# lab2_kuchenov_buck.net
KiCad netlist of a schematic drawn in Altium Designer
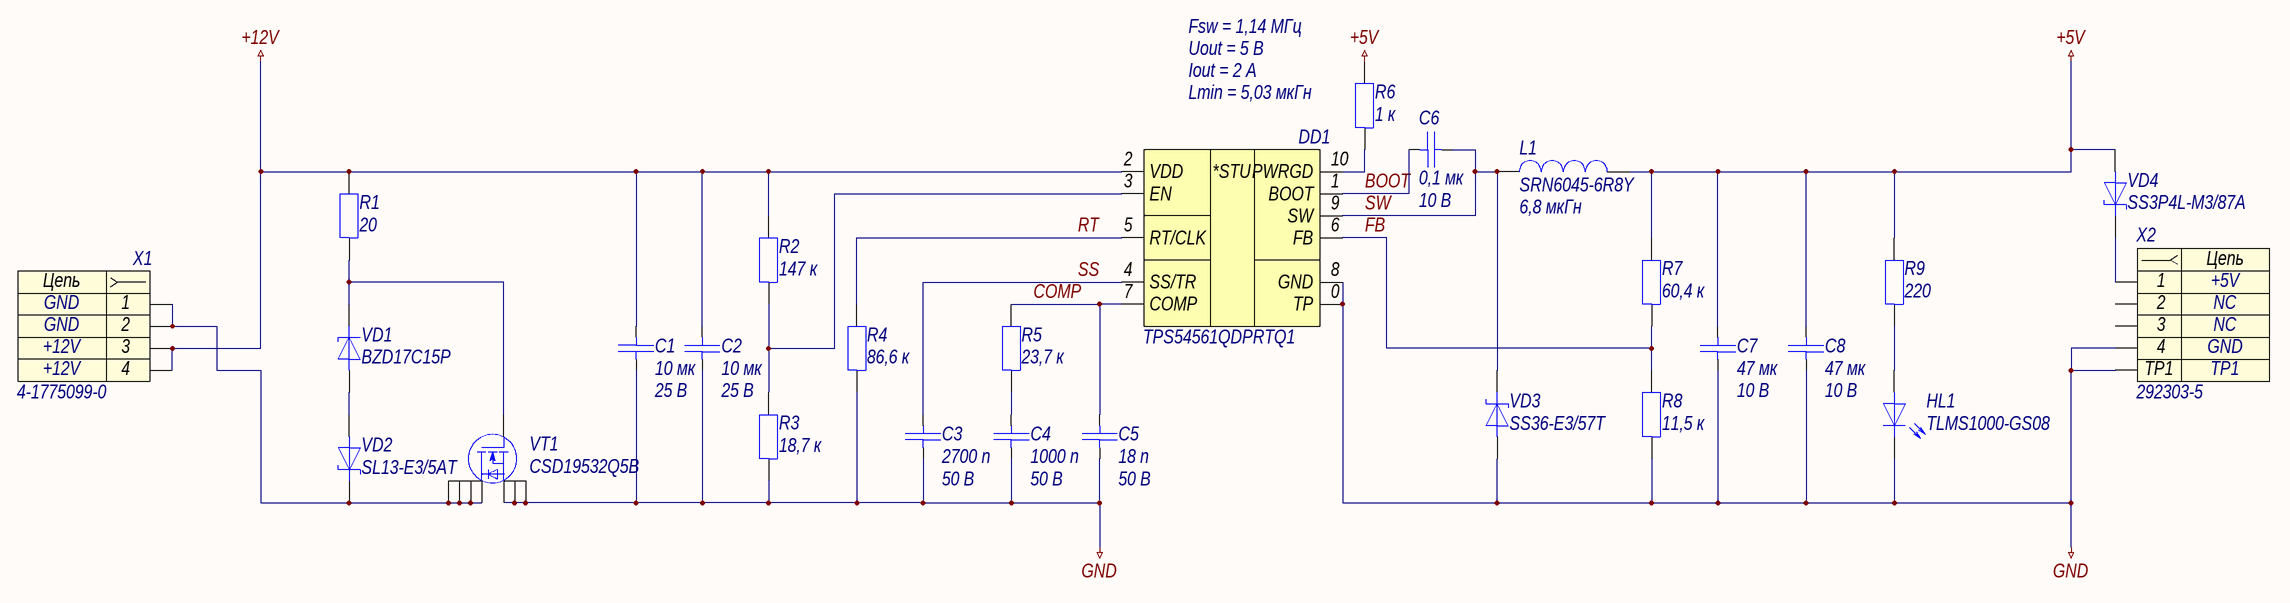
[diagram p0: lab2_kuchenov_buck.SchDoc]

(export (version "E")
  (design (tool "Eeschema 10.0.6"))
  (components
    (comp (ref "C1")
      (value "10 мк")
      (footprint "C0805")
      (description "=Описание")
      (fields (field (name "НАПРЯЖЕНИЕ") "25 В"))
      (libsource (lib "Database_Students") (part "C-NONPOLAR"))
    )
    (comp (ref "C2")
      (value "10 мк")
      (footprint "C0805")
      (description "=Описание")
      (fields (field (name "НАПРЯЖЕНИЕ") "25 В"))
      (libsource (lib "Database_Students") (part "C-NONPOLAR"))
    )
    (comp (ref "C3")
      (value "2700 п")
      (footprint "C0805")
      (description "=Описание")
      (fields (field (name "НАПРЯЖЕНИЕ") "50 В"))
      (libsource (lib "Database_Students") (part "C-NONPOLAR"))
    )
    (comp (ref "C4")
      (value "1000 п")
      (footprint "C0402")
      (description "=Описание")
      (fields (field (name "НАПРЯЖЕНИЕ") "50 В"))
      (libsource (lib "Database_Students") (part "C-NONPOLAR"))
    )
    (comp (ref "C5")
      (value "18 п")
      (footprint "C0805")
      (description "=Описание")
      (fields (field (name "НАПРЯЖЕНИЕ") "50 В"))
      (libsource (lib "Database_Students") (part "C-NONPOLAR"))
    )
    (comp (ref "C6")
      (value "0,1 мк")
      (footprint "C0402")
      (description "=Описание")
      (fields (field (name "НАПРЯЖЕНИЕ") "10 В"))
      (libsource (lib "Database_Students") (part "C-NONPOLAR"))
    )
    (comp (ref "C7")
      (value "47 мк")
      (footprint "C1210")
      (description "=Описание")
      (fields (field (name "НАПРЯЖЕНИЕ") "10 В"))
      (libsource (lib "Database_Students") (part "C-NONPOLAR"))
    )
    (comp (ref "C8")
      (value "47 мк")
      (footprint "C1210")
      (description "=Описание")
      (fields (field (name "НАПРЯЖЕНИЕ") "10 В"))
      (libsource (lib "Database_Students") (part "C-NONPOLAR"))
    )
    (comp (ref "DD1")
      (value "TPS54561QDPRTQ1")
      (footprint "WSON-10-400X400X80")
      (description "=Описание")
      (libsource (lib "Database_Students") (part "TPS54561QDPRTQ1"))
    )
    (comp (ref "HL1")
      (value "TLMS1000-GS08")
      (footprint "HL0603")
      (description "=Описание")
      (libsource (lib "Database_Students") (part "HL-COMMON"))
    )
    (comp (ref "L1")
      (value "SRN6045-6R8Y")
      (footprint "SRN-2-600X600X450")
      (description "=Описание")
      (fields (field (name "ИНДУКТИВНОСТЬ") "6,8 мкГн"))
      (libsource (lib "Database_Students") (part "INDUCTOR-COMMON"))
    )
    (comp (ref "R1")
      (value "20")
      (footprint "R0402")
      (description "=Описание")
      (libsource (lib "Database_Students") (part "R-COMMON"))
    )
    (comp (ref "R2")
      (value "147 к")
      (footprint "R0603")
      (description "=Описание")
      (libsource (lib "Database_Students") (part "R-COMMON"))
    )
    (comp (ref "R3")
      (value "18,7 к")
      (footprint "R0402")
      (description "=Описание")
      (libsource (lib "Database_Students") (part "R-COMMON"))
    )
    (comp (ref "R4")
      (value "86,6 к")
      (footprint "R0201")
      (description "=Описание")
      (libsource (lib "Database_Students") (part "R-COMMON"))
    )
    (comp (ref "R5")
      (value "23,7 к")
      (footprint "R0201")
      (description "=Описание")
      (libsource (lib "Database_Students") (part "R-COMMON"))
    )
    (comp (ref "R6")
      (value "1 к")
      (footprint "R0402")
      (description "=Описание")
      (libsource (lib "Database_Students") (part "R-COMMON"))
    )
    (comp (ref "R7")
      (value "60,4 к")
      (footprint "R0402")
      (description "=Описание")
      (libsource (lib "Database_Students") (part "R-COMMON"))
    )
    (comp (ref "R8")
      (value "11,5 к")
      (footprint "R0402")
      (description "=Описание")
      (libsource (lib "Database_Students") (part "R-COMMON"))
    )
    (comp (ref "R9")
      (value "220")
      (footprint "R0603")
      (description "=Описание")
      (libsource (lib "Database_Students") (part "R-COMMON"))
    )
    (comp (ref "VD1")
      (value "BZD17C15P")
      (footprint "DO-219AB")
      (description "=Описание")
      (libsource (lib "Database_Students") (part "ZENER-DIODE"))
    )
    (comp (ref "VD2")
      (value "SL13-E3/5AT")
      (footprint "DO-214AC")
      (description "=Описание")
      (libsource (lib "Database_Students") (part "DIODE-SCHOTTKY"))
    )
    (comp (ref "VD3")
      (value "SS36-E3/57T")
      (footprint "DO-214AB")
      (description "=Описание")
      (libsource (lib "Database_Students") (part "DIODE-SCHOTTKY"))
    )
    (comp (ref "VD4")
      (value "SS3P4L-M3/87A")
      (footprint "TO-277A")
      (description "=Описание")
      (libsource (lib "Database_Students") (part "DIODE-SCHOTTKY"))
    )
    (comp (ref "VT1")
      (value "CSD19532Q5B")
      (footprint "SON-8")
      (description "=Описание")
      (libsource (lib "Database_Students") (part "MOSFET-N-1G-3S-4D"))
    )
    (comp (ref "X1")
      (value "4-1775099-0")
      (footprint "4-1775099-0")
      (description "=Описание")
      (libsource (lib "Database_Students") (part "HEADER-4-SCT"))
    )
    (comp (ref "X2")
      (value "292303-5")
      (footprint "292303-5")
      (description "=Описание")
      (libsource (lib "Database_Students") (part "HEADER-4-TP1-SCT"))
    )
  )
  (nets
    (net (code "1") (name "+5V") (class "Default")
      (node (ref "C7") (pin "1") (pinfunction "1_1") (pintype "passive"))
      (node (ref "C8") (pin "1") (pinfunction "1_1") (pintype "passive"))
      (node (ref "L1") (pin "2") (pinfunction "2_2") (pintype "passive"))
      (node (ref "R6") (pin "2") (pinfunction "2_2") (pintype "passive"))
      (node (ref "R7") (pin "2") (pinfunction "2_2") (pintype "passive"))
      (node (ref "R9") (pin "2") (pinfunction "2_2") (pintype "passive"))
      (node (ref "VD4") (pin "2") (pinfunction "2_2") (pintype "passive"))
    )
    (net (code "2") (name "+12V") (class "Default")
      (node (ref "C1") (pin "2") (pinfunction "2_2") (pintype "passive"))
      (node (ref "C2") (pin "1") (pinfunction "1_1") (pintype "passive"))
      (node (ref "DD1") (pin "2") (pinfunction "VDD_2") (pintype "passive"))
      (node (ref "R1") (pin "2") (pinfunction "2_2") (pintype "passive"))
      (node (ref "R2") (pin "2") (pinfunction "2_2") (pintype "passive"))
      (node (ref "X1") (pin "3") (pinfunction "3_3") (pintype "passive"))
      (node (ref "X1") (pin "4") (pinfunction "4_4") (pintype "passive"))
    )
    (net (code "3") (name "/BOOT") (class "Default")
      (node (ref "C6") (pin "2") (pinfunction "2_2") (pintype "passive"))
      (node (ref "DD1") (pin "1") (pinfunction "BOOT_1") (pintype "passive"))
    )
    (net (code "4") (name "/COMP") (class "Default")
      (node (ref "C5") (pin "1") (pinfunction "1_1") (pintype "passive"))
      (node (ref "DD1") (pin "7") (pinfunction "COMP_7") (pintype "passive"))
      (node (ref "R5") (pin "2") (pinfunction "2_2") (pintype "passive"))
    )
    (net (code "5") (name "/FB") (class "Default")
      (node (ref "DD1") (pin "6") (pinfunction "FB_6") (pintype "passive"))
      (node (ref "R7") (pin "1") (pinfunction "1_1") (pintype "passive"))
      (node (ref "R8") (pin "2") (pinfunction "2_2") (pintype "passive"))
    )
    (net (code "6") (name "/RT") (class "Default")
      (node (ref "DD1") (pin "5") (pinfunction "RT/CLK_5") (pintype "passive"))
      (node (ref "R4") (pin "2") (pinfunction "2_2") (pintype "passive"))
    )
    (net (code "7") (name "/SS") (class "Default")
      (node (ref "C3") (pin "1") (pinfunction "1_1") (pintype "passive"))
      (node (ref "DD1") (pin "4") (pinfunction "SS/TR_4") (pintype "passive"))
    )
    (net (code "8") (name "/SW") (class "Default")
      (node (ref "C6") (pin "1") (pinfunction "1_1") (pintype "passive"))
      (node (ref "DD1") (pin "9") (pinfunction "SW_9") (pintype "passive"))
      (node (ref "L1") (pin "1") (pinfunction "1_1") (pintype "passive"))
      (node (ref "VD3") (pin "1") (pinfunction "1_1") (pintype "passive"))
    )
    (net (code "9") (name "GND") (class "Default")
      (node (ref "C1") (pin "1") (pinfunction "1_1") (pintype "passive"))
      (node (ref "C2") (pin "2") (pinfunction "2_2") (pintype "passive"))
      (node (ref "C3") (pin "2") (pinfunction "2_2") (pintype "passive"))
      (node (ref "C4") (pin "2") (pinfunction "2_2") (pintype "passive"))
      (node (ref "C5") (pin "2") (pinfunction "2_2") (pintype "passive"))
      (node (ref "C7") (pin "2") (pinfunction "2_2") (pintype "passive"))
      (node (ref "C8") (pin "2") (pinfunction "2_2") (pintype "passive"))
      (node (ref "DD1") (pin "0") (pinfunction "TP_0") (pintype "passive"))
      (node (ref "DD1") (pin "8") (pinfunction "GND_8") (pintype "passive"))
      (node (ref "HL1") (pin "1") (pinfunction "1_1") (pintype "passive"))
      (node (ref "R3") (pin "1") (pinfunction "1_1") (pintype "passive"))
      (node (ref "R4") (pin "1") (pinfunction "1_1") (pintype "passive"))
      (node (ref "R8") (pin "1") (pinfunction "1_1") (pintype "passive"))
      (node (ref "VD3") (pin "2") (pinfunction "2_2") (pintype "passive"))
      (node (ref "VT1") (pin "S") (pinfunction "S_S") (pintype "passive"))
      (node (ref "X2") (pin "4") (pinfunction "4_4") (pintype "passive"))
      (node (ref "X2") (pin "TP1") (pinfunction "TP1_TP1") (pintype "passive"))
    )
    (net (code "10") (name "Net-(C4-Pad1)") (class "Default")
      (node (ref "C4") (pin "1") (pinfunction "1_1") (pintype "passive"))
      (node (ref "R5") (pin "1") (pinfunction "1_1") (pintype "passive"))
    )
    (net (code "11") (name "Net-(DD1-EN)") (class "Default")
      (node (ref "DD1") (pin "3") (pinfunction "EN_3") (pintype "passive"))
      (node (ref "R2") (pin "1") (pinfunction "1_1") (pintype "passive"))
      (node (ref "R3") (pin "2") (pinfunction "2_2") (pintype "passive"))
    )
    (net (code "12") (name "Net-(DD1-PWRGD)") (class "Default")
      (node (ref "DD1") (pin "10") (pinfunction "PWRGD_10") (pintype "passive"))
      (node (ref "R6") (pin "1") (pinfunction "1_1") (pintype "passive"))
    )
    (net (code "13") (name "Net-(HL1-Pad2)") (class "Default")
      (node (ref "HL1") (pin "2") (pinfunction "2_2") (pintype "passive"))
      (node (ref "R9") (pin "1") (pinfunction "1_1") (pintype "passive"))
    )
    (net (code "14") (name "Net-(R1-Pad1)") (class "Default")
      (node (ref "R1") (pin "1") (pinfunction "1_1") (pintype "passive"))
      (node (ref "VD1") (pin "1") (pinfunction "1_1") (pintype "passive"))
      (node (ref "VT1") (pin "G") (pinfunction "G_G") (pintype "passive"))
    )
    (net (code "15") (name "Net-(VD1-Pad2)") (class "Default")
      (node (ref "VD1") (pin "2") (pinfunction "2_2") (pintype "passive"))
      (node (ref "VD2") (pin "2") (pinfunction "2_2") (pintype "passive"))
    )
    (net (code "16") (name "Net-(VD2-Pad1)") (class "Default")
      (node (ref "VD2") (pin "1") (pinfunction "1_1") (pintype "passive"))
      (node (ref "VT1") (pin "D") (pinfunction "D_D") (pintype "passive"))
      (node (ref "X1") (pin "1") (pinfunction "1_1") (pintype "passive"))
      (node (ref "X1") (pin "2") (pinfunction "2_2") (pintype "passive"))
    )
    (net (code "17") (name "Net-(VD4-Pad1)") (class "Default")
      (node (ref "VD4") (pin "1") (pinfunction "1_1") (pintype "passive"))
      (node (ref "X2") (pin "1") (pinfunction "1_1") (pintype "passive"))
    )
    (net (code "18") (name "unconnected-(X2-Pad2)") (class "Default")
      (node (ref "X2") (pin "2") (pinfunction "2_2") (pintype "passive"))
    )
    (net (code "19") (name "unconnected-(X2-Pad3)") (class "Default")
      (node (ref "X2") (pin "3") (pinfunction "3_3") (pintype "passive"))
    )
  )
)
